# TachometerModule.net
KiCad netlist of a schematic drawn in Altium Designer
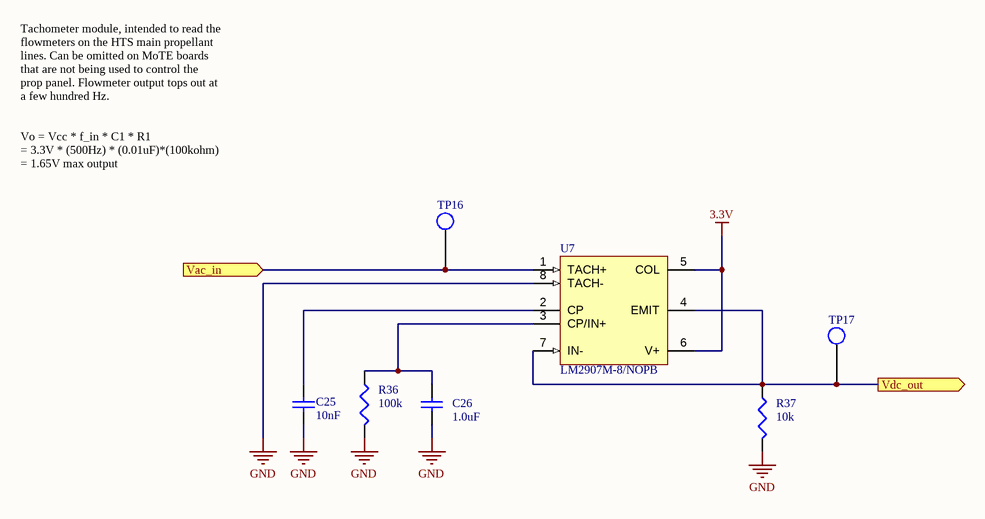
[diagram p0: TachometerModule.SchDoc]

(export (version "E")
  (design (tool "Eeschema 10.0.6"))
  (components
    (comp (ref "C25")
      (value "10nF")
      (footprint "1608[0603]")
      (description "Capacitor")
      (fields (field (name "Comment") "Cap") (field (name "PUBLISHER") "Altium Limited"))
      (libsource (lib "Miscellaneous Devices") (part "Cap"))
    )
    (comp (ref "C26")
      (value "1.0uF")
      (footprint "1608[0603]")
      (description "low ESR film cap")
      (fields (field (name "Comment") "a") (field (name "PUBLISHER") "Altium Limited"))
      (libsource (lib "Miscellaneous Devices") (part "Cap"))
    )
    (comp (ref "R36")
      (value "100k")
      (footprint "J1-0603")
      (description "Resistor")
      (fields (field (name "Comment") "Res3") (field (name "PUBLISHER") "Altium Limited"))
      (libsource (lib "Miscellaneous Devices") (part "Res3"))
    )
    (comp (ref "R37")
      (value "10k")
      (footprint "J1-0603")
      (description "Resistor")
      (fields (field (name "Comment") "Res3") (field (name "PUBLISHER") "Altium Limited"))
      (libsource (lib "Miscellaneous Devices") (part "Res3"))
    )
    (comp (ref "TP16")
      (value "BURPG_TestPoint1")
      (footprint "BURPG_TestPoint1")
      (libsource (lib "BURPG_generic") (part "BURPG_TestPoint1"))
    )
    (comp (ref "TP17")
      (value "BURPG_TestPoint1")
      (footprint "BURPG_TestPoint1")
      (libsource (lib "BURPG_generic") (part "BURPG_TestPoint1"))
    )
    (comp (ref "U7")
      (value "LM2907M-8/NOPB")
      (footprint "D0008A_L")
      (description "Frequency to Voltage Converter, 8-pin Narrow SOIC, Pb-Free")
      (fields (field (name "MANUFACTURER") "Texas Instruments"))
      (libsource (lib "Altium Content Vault") (part "CON-FVC-LM2907-IL8"))
    )
  )
  (nets
    (net (code "1") (name "/Vac_in") (class "Default")
      (node (ref "TP16") (pin "1") (pinfunction "1_1") (pintype "passive"))
      (node (ref "U7") (pin "1") (pinfunction "TACH+_1") (pintype "input"))
    )
    (net (code "2") (name "/Vdc_out") (class "Default")
      (node (ref "R37") (pin "1") (pinfunction "1_1") (pintype "passive"))
      (node (ref "TP17") (pin "1") (pinfunction "1_1") (pintype "passive"))
      (node (ref "U7") (pin "4") (pinfunction "EMIT_4") (pintype "passive"))
      (node (ref "U7") (pin "7") (pinfunction "IN-_7") (pintype "input"))
    )
    (net (code "3") (name "3.3V") (class "Default")
      (node (ref "U7") (pin "5") (pinfunction "COL_5") (pintype "passive"))
      (node (ref "U7") (pin "6") (pinfunction "V+_6") (pintype "power_in"))
    )
    (net (code "4") (name "GND") (class "Default")
      (node (ref "C25") (pin "2") (pinfunction "2_2") (pintype "passive"))
      (node (ref "C26") (pin "1") (pinfunction "1_1") (pintype "passive"))
      (node (ref "R36") (pin "2") (pinfunction "2_2") (pintype "passive"))
      (node (ref "R37") (pin "2") (pinfunction "2_2") (pintype "passive"))
      (node (ref "U7") (pin "8") (pinfunction "TACH-_8") (pintype "input"))
    )
    (net (code "5") (name "Net-(U7-CP)") (class "Default")
      (node (ref "C25") (pin "1") (pinfunction "1_1") (pintype "passive"))
      (node (ref "U7") (pin "2") (pinfunction "CP_2") (pintype "passive"))
    )
    (net (code "6") (name "Net-(U7-CP{slash}IN+)") (class "Default")
      (node (ref "C26") (pin "2") (pinfunction "2_2") (pintype "passive"))
      (node (ref "R36") (pin "1") (pinfunction "1_1") (pintype "passive"))
      (node (ref "U7") (pin "3") (pinfunction "CP/IN+_3") (pintype "passive"))
    )
  )
)
